# untitled.net
KiCad netlist of a schematic drawn in EAGLE
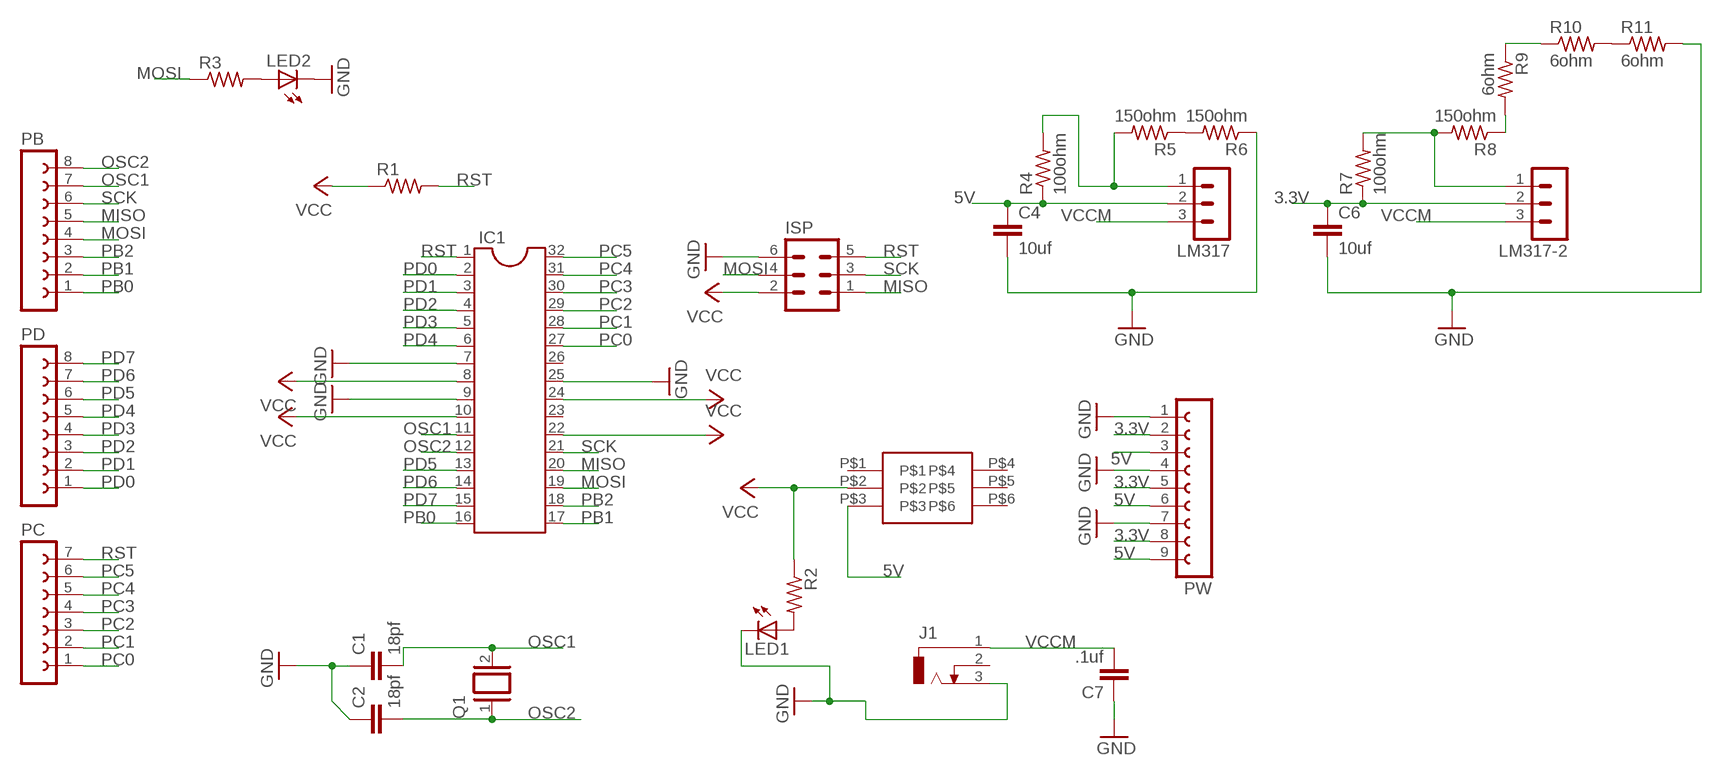
[diagram p0: schematic, sheet 1]

(export (version "E")
  (design (tool "Eeschema 10.0.6"))
  (components
    (comp (ref "C1")
      (value "18pf")
      (footprint "eagle-import:C2.5-2")
      (libsource (lib "eagle-import") (part "C2.5/2"))
    )
    (comp (ref "C2")
      (value "18pf")
      (footprint "eagle-import:C2.5-2")
      (libsource (lib "eagle-import") (part "C2.5/2"))
    )
    (comp (ref "C4")
      (value "10uf")
      (footprint "eagle-import:C15B5")
      (libsource (lib "eagle-import") (part "C15/5"))
    )
    (comp (ref "C6")
      (value "10uf")
      (footprint "eagle-import:C15B5")
      (libsource (lib "eagle-import") (part "C15/5"))
    )
    (comp (ref "C7")
      (value ".1uf")
      (footprint "eagle-import:C5B2.5")
      (libsource (lib "eagle-import") (part "C5/2.5"))
    )
    (comp (ref "IC1")
      (value "DIL32")
      (footprint "eagle-import:DIL32")
      (libsource (lib "eagle-import") (part "DIL32"))
    )
    (comp (ref "ISP")
      (value "MA03-2")
      (footprint "eagle-import:MA03-2")
      (libsource (lib "eagle-import") (part "MA03-2"))
    )
    (comp (ref "J1")
      (value "DCJ0303")
      (footprint "eagle-import:DCJ0303")
      (libsource (lib "eagle-import") (part "DCJ0303"))
    )
    (comp (ref "LED1")
      (value "LED3MM")
      (footprint "eagle-import:LED3MM")
      (libsource (lib "eagle-import") (part "LED3MM"))
    )
    (comp (ref "LED2")
      (value "LED5MM")
      (footprint "eagle-import:LED5MM")
      (libsource (lib "eagle-import") (part "LED5MM"))
    )
    (comp (ref "LM317")
      (value "MA03-1")
      (footprint "eagle-import:MA03-1")
      (libsource (lib "eagle-import") (part "MA03-1"))
    )
    (comp (ref "LM317-2")
      (value "MA03-1")
      (footprint "eagle-import:MA03-1")
      (libsource (lib "eagle-import") (part "MA03-1"))
    )
    (comp (ref "PB")
      (value "FE08-1")
      (footprint "eagle-import:FE08")
      (libsource (lib "eagle-import") (part "FE08-1"))
    )
    (comp (ref "PC")
      (value "FE07-1")
      (footprint "eagle-import:FE07")
      (libsource (lib "eagle-import") (part "FE07-1"))
    )
    (comp (ref "PD")
      (value "FE08-1")
      (footprint "eagle-import:FE08")
      (libsource (lib "eagle-import") (part "FE08-1"))
    )
    (comp (ref "PW")
      (value "FE09-1")
      (footprint "eagle-import:FE09")
      (libsource (lib "eagle-import") (part "FE09-1"))
    )
    (comp (ref "Q1")
      (value "XTAL/S")
      (footprint "eagle-import:QS")
      (libsource (lib "eagle-import") (part "XTAL/S"))
    )
    (comp (ref "R1")
      (value "R-US_0207/10")
      (footprint "eagle-import:0207_10")
      (libsource (lib "eagle-import") (part "R-US_0207/10"))
    )
    (comp (ref "R2")
      (value "R-US_0207/10")
      (footprint "eagle-import:0207_10")
      (libsource (lib "eagle-import") (part "R-US_0207/10"))
    )
    (comp (ref "R3")
      (value "R-US_0207/10")
      (footprint "eagle-import:0207_10")
      (libsource (lib "eagle-import") (part "R-US_0207/10"))
    )
    (comp (ref "R4")
      (value "100ohm")
      (footprint "eagle-import:0207_10")
      (fields (field (name "MF") "Multicomp Passives") (field (name "MPN") "MC00625W04021220R"))
      (libsource (lib "eagle-import") (part "R-US_0207/10"))
    )
    (comp (ref "R5")
      (value "150ohm")
      (footprint "eagle-import:0207_10")
      (libsource (lib "eagle-import") (part "R-US_0207/10"))
    )
    (comp (ref "R6")
      (value "150ohm")
      (footprint "eagle-import:0207_10")
      (libsource (lib "eagle-import") (part "R-US_0207/10"))
    )
    (comp (ref "R7")
      (value "100ohm")
      (footprint "eagle-import:0207_10")
      (fields (field (name "MF") "Multicomp Passives") (field (name "MPN") "MC00625W04021220R"))
      (libsource (lib "eagle-import") (part "R-US_0207/10"))
    )
    (comp (ref "R8")
      (value "150ohm")
      (footprint "eagle-import:0207_10")
      (libsource (lib "eagle-import") (part "R-US_0207/10"))
    )
    (comp (ref "R9")
      (value "6ohm")
      (footprint "eagle-import:0207_10")
      (libsource (lib "eagle-import") (part "R-US_0207/10"))
    )
    (comp (ref "R10")
      (value "6ohm")
      (footprint "eagle-import:0207_10")
      (libsource (lib "eagle-import") (part "R-US_0207/10"))
    )
    (comp (ref "R11")
      (value "6ohm")
      (footprint "eagle-import:0207_10")
      (libsource (lib "eagle-import") (part "R-US_0207/10"))
    )
    (comp (ref "U$1")
      (value "6PINPUSHSC2BIGJOE-CUSTOM")
      (footprint "eagle-import:6PINPUSH")
      (libsource (lib "eagle-import") (part "6PINPUSHSC2BIGJOE-CUSTOM"))
    )
  )
  (nets
    (net (code "1") (name "/3.3V") (class "Default")
      (node (ref "C6") (pin "1") (pinfunction "1_1") (pintype "passive"))
      (node (ref "LM317-2") (pin "2") (pinfunction "2_2") (pintype "passive"))
      (node (ref "PW") (pin "2") (pinfunction "2_2") (pintype "passive"))
      (node (ref "PW") (pin "5") (pinfunction "5_5") (pintype "passive"))
      (node (ref "PW") (pin "8") (pinfunction "8_8") (pintype "passive"))
      (node (ref "R7") (pin "1") (pinfunction "1_1") (pintype "passive"))
    )
    (net (code "2") (name "/5V") (class "Default")
      (node (ref "C4") (pin "1") (pinfunction "1_1") (pintype "passive"))
      (node (ref "LM317") (pin "2") (pinfunction "2_2") (pintype "passive"))
      (node (ref "PW") (pin "3") (pinfunction "3_3") (pintype "passive"))
      (node (ref "PW") (pin "6") (pinfunction "6_6") (pintype "passive"))
      (node (ref "PW") (pin "9") (pinfunction "9_9") (pintype "passive"))
      (node (ref "R4") (pin "1") (pinfunction "1_1") (pintype "passive"))
      (node (ref "U$1") (pin "P$3") (pinfunction "P$3_P$3") (pintype "bidirectional"))
    )
    (net (code "3") (name "/MISO") (class "Default")
      (node (ref "IC1") (pin "20") (pinfunction "20_20") (pintype "passive"))
      (node (ref "ISP") (pin "1") (pinfunction "1_1") (pintype "passive"))
      (node (ref "PB") (pin "5") (pinfunction "5_5") (pintype "passive"))
    )
    (net (code "4") (name "/MOSI") (class "Default")
      (node (ref "IC1") (pin "19") (pinfunction "19_19") (pintype "passive"))
      (node (ref "ISP") (pin "4") (pinfunction "4_4") (pintype "passive"))
      (node (ref "PB") (pin "4") (pinfunction "4_4") (pintype "passive"))
      (node (ref "R3") (pin "1") (pinfunction "1_1") (pintype "passive"))
    )
    (net (code "5") (name "/OSC1") (class "Default")
      (node (ref "C1") (pin "2") (pinfunction "2_2") (pintype "passive"))
      (node (ref "IC1") (pin "11") (pinfunction "11_11") (pintype "passive"))
      (node (ref "PB") (pin "7") (pinfunction "7_7") (pintype "passive"))
      (node (ref "Q1") (pin "2") (pinfunction "2_2") (pintype "passive"))
    )
    (net (code "6") (name "/OSC2") (class "Default")
      (node (ref "C2") (pin "2") (pinfunction "2_2") (pintype "passive"))
      (node (ref "IC1") (pin "12") (pinfunction "12_12") (pintype "passive"))
      (node (ref "PB") (pin "8") (pinfunction "8_8") (pintype "passive"))
      (node (ref "Q1") (pin "1") (pinfunction "1_1") (pintype "passive"))
    )
    (net (code "7") (name "/PB0") (class "Default")
      (node (ref "IC1") (pin "16") (pinfunction "16_16") (pintype "passive"))
      (node (ref "PB") (pin "1") (pinfunction "1_1") (pintype "passive"))
    )
    (net (code "8") (name "/PB1") (class "Default")
      (node (ref "IC1") (pin "17") (pinfunction "17_17") (pintype "passive"))
      (node (ref "PB") (pin "2") (pinfunction "2_2") (pintype "passive"))
    )
    (net (code "9") (name "/PB2") (class "Default")
      (node (ref "IC1") (pin "18") (pinfunction "18_18") (pintype "passive"))
      (node (ref "PB") (pin "3") (pinfunction "3_3") (pintype "passive"))
    )
    (net (code "10") (name "/PC0") (class "Default")
      (node (ref "IC1") (pin "27") (pinfunction "27_27") (pintype "passive"))
      (node (ref "PC") (pin "1") (pinfunction "1_1") (pintype "passive"))
    )
    (net (code "11") (name "/PC1") (class "Default")
      (node (ref "IC1") (pin "28") (pinfunction "28_28") (pintype "passive"))
      (node (ref "PC") (pin "2") (pinfunction "2_2") (pintype "passive"))
    )
    (net (code "12") (name "/PC2") (class "Default")
      (node (ref "IC1") (pin "29") (pinfunction "29_29") (pintype "passive"))
      (node (ref "PC") (pin "3") (pinfunction "3_3") (pintype "passive"))
    )
    (net (code "13") (name "/PC3") (class "Default")
      (node (ref "IC1") (pin "30") (pinfunction "30_30") (pintype "passive"))
      (node (ref "PC") (pin "4") (pinfunction "4_4") (pintype "passive"))
    )
    (net (code "14") (name "/PC4") (class "Default")
      (node (ref "IC1") (pin "31") (pinfunction "31_31") (pintype "passive"))
      (node (ref "PC") (pin "5") (pinfunction "5_5") (pintype "passive"))
    )
    (net (code "15") (name "/PC5") (class "Default")
      (node (ref "IC1") (pin "32") (pinfunction "32_32") (pintype "passive"))
      (node (ref "PC") (pin "6") (pinfunction "6_6") (pintype "passive"))
    )
    (net (code "16") (name "/PD0") (class "Default")
      (node (ref "IC1") (pin "2") (pinfunction "2_2") (pintype "passive"))
      (node (ref "PD") (pin "1") (pinfunction "1_1") (pintype "passive"))
    )
    (net (code "17") (name "/PD1") (class "Default")
      (node (ref "IC1") (pin "3") (pinfunction "3_3") (pintype "passive"))
      (node (ref "PD") (pin "2") (pinfunction "2_2") (pintype "passive"))
    )
    (net (code "18") (name "/PD2") (class "Default")
      (node (ref "IC1") (pin "4") (pinfunction "4_4") (pintype "passive"))
      (node (ref "PD") (pin "3") (pinfunction "3_3") (pintype "passive"))
    )
    (net (code "19") (name "/PD3") (class "Default")
      (node (ref "IC1") (pin "5") (pinfunction "5_5") (pintype "passive"))
      (node (ref "PD") (pin "4") (pinfunction "4_4") (pintype "passive"))
    )
    (net (code "20") (name "/PD4") (class "Default")
      (node (ref "IC1") (pin "6") (pinfunction "6_6") (pintype "passive"))
      (node (ref "PD") (pin "5") (pinfunction "5_5") (pintype "passive"))
    )
    (net (code "21") (name "/PD5") (class "Default")
      (node (ref "IC1") (pin "13") (pinfunction "13_13") (pintype "passive"))
      (node (ref "PD") (pin "6") (pinfunction "6_6") (pintype "passive"))
    )
    (net (code "22") (name "/PD6") (class "Default")
      (node (ref "IC1") (pin "14") (pinfunction "14_14") (pintype "passive"))
      (node (ref "PD") (pin "7") (pinfunction "7_7") (pintype "passive"))
    )
    (net (code "23") (name "/PD7") (class "Default")
      (node (ref "IC1") (pin "15") (pinfunction "15_15") (pintype "passive"))
      (node (ref "PD") (pin "8") (pinfunction "8_8") (pintype "passive"))
    )
    (net (code "24") (name "/RST") (class "Default")
      (node (ref "IC1") (pin "1") (pinfunction "1_1") (pintype "passive"))
      (node (ref "ISP") (pin "5") (pinfunction "5_5") (pintype "passive"))
      (node (ref "PC") (pin "7") (pinfunction "7_7") (pintype "passive"))
      (node (ref "R1") (pin "2") (pinfunction "2_2") (pintype "passive"))
    )
    (net (code "25") (name "/SCK") (class "Default")
      (node (ref "IC1") (pin "21") (pinfunction "21_21") (pintype "passive"))
      (node (ref "ISP") (pin "3") (pinfunction "3_3") (pintype "passive"))
      (node (ref "PB") (pin "6") (pinfunction "6_6") (pintype "passive"))
    )
    (net (code "26") (name "/VCCM") (class "Default")
      (node (ref "C7") (pin "2") (pinfunction "2_2") (pintype "passive"))
      (node (ref "J1") (pin "1") (pinfunction "1_1") (pintype "passive"))
      (node (ref "LM317") (pin "3") (pinfunction "3_3") (pintype "passive"))
      (node (ref "LM317-2") (pin "3") (pinfunction "3_3") (pintype "passive"))
    )
    (net (code "27") (name "GND") (class "Default")
      (node (ref "C1") (pin "1") (pinfunction "1_1") (pintype "passive"))
      (node (ref "C2") (pin "1") (pinfunction "1_1") (pintype "passive"))
      (node (ref "C4") (pin "2") (pinfunction "2_2") (pintype "passive"))
      (node (ref "C6") (pin "2") (pinfunction "2_2") (pintype "passive"))
      (node (ref "C7") (pin "1") (pinfunction "1_1") (pintype "passive"))
      (node (ref "IC1") (pin "25") (pinfunction "25_25") (pintype "passive"))
      (node (ref "IC1") (pin "7") (pinfunction "7_7") (pintype "passive"))
      (node (ref "IC1") (pin "9") (pinfunction "9_9") (pintype "passive"))
      (node (ref "ISP") (pin "6") (pinfunction "6_6") (pintype "passive"))
      (node (ref "J1") (pin "3") (pinfunction "3_3") (pintype "passive"))
      (node (ref "LED1") (pin "K") (pinfunction "C_K") (pintype "passive"))
      (node (ref "LED2") (pin "K") (pinfunction "C_K") (pintype "passive"))
      (node (ref "PW") (pin "1") (pinfunction "1_1") (pintype "passive"))
      (node (ref "PW") (pin "4") (pinfunction "4_4") (pintype "passive"))
      (node (ref "PW") (pin "7") (pinfunction "7_7") (pintype "passive"))
      (node (ref "R11") (pin "2") (pinfunction "2_2") (pintype "passive"))
      (node (ref "R6") (pin "1") (pinfunction "1_1") (pintype "passive"))
    )
    (net (code "28") (name "Net-(LED1-PadA)") (class "Default")
      (node (ref "LED1") (pin "A") (pinfunction "A_A") (pintype "passive"))
      (node (ref "R2") (pin "2") (pinfunction "2_2") (pintype "passive"))
    )
    (net (code "29") (name "Net-(LED2-PadA)") (class "Default")
      (node (ref "LED2") (pin "A") (pinfunction "A_A") (pintype "passive"))
      (node (ref "R3") (pin "2") (pinfunction "2_2") (pintype "passive"))
    )
    (net (code "30") (name "Net-(LM317-2-Pad1)") (class "Default")
      (node (ref "LM317-2") (pin "1") (pinfunction "1_1") (pintype "passive"))
      (node (ref "R7") (pin "2") (pinfunction "2_2") (pintype "passive"))
      (node (ref "R8") (pin "2") (pinfunction "2_2") (pintype "passive"))
    )
    (net (code "31") (name "Net-(LM317-Pad1)") (class "Default")
      (node (ref "LM317") (pin "1") (pinfunction "1_1") (pintype "passive"))
      (node (ref "R4") (pin "2") (pinfunction "2_2") (pintype "passive"))
      (node (ref "R5") (pin "2") (pinfunction "2_2") (pintype "passive"))
    )
    (net (code "32") (name "Net-(R5-Pad1)") (class "Default")
      (node (ref "R5") (pin "1") (pinfunction "1_1") (pintype "passive"))
      (node (ref "R6") (pin "2") (pinfunction "2_2") (pintype "passive"))
    )
    (net (code "33") (name "Net-(R8-Pad1)") (class "Default")
      (node (ref "R8") (pin "1") (pinfunction "1_1") (pintype "passive"))
      (node (ref "R9") (pin "2") (pinfunction "2_2") (pintype "passive"))
    )
    (net (code "34") (name "Net-(R10-Pad1)") (class "Default")
      (node (ref "R10") (pin "1") (pinfunction "1_1") (pintype "passive"))
      (node (ref "R9") (pin "1") (pinfunction "1_1") (pintype "passive"))
    )
    (net (code "35") (name "Net-(R10-Pad2)") (class "Default")
      (node (ref "R10") (pin "2") (pinfunction "2_2") (pintype "passive"))
      (node (ref "R11") (pin "1") (pinfunction "1_1") (pintype "passive"))
    )
    (net (code "36") (name "VCC") (class "Default")
      (node (ref "IC1") (pin "10") (pinfunction "10_10") (pintype "passive"))
      (node (ref "IC1") (pin "22") (pinfunction "22_22") (pintype "passive"))
      (node (ref "IC1") (pin "24") (pinfunction "24_24") (pintype "passive"))
      (node (ref "IC1") (pin "8") (pinfunction "8_8") (pintype "passive"))
      (node (ref "ISP") (pin "2") (pinfunction "2_2") (pintype "passive"))
      (node (ref "R1") (pin "1") (pinfunction "1_1") (pintype "passive"))
      (node (ref "R2") (pin "1") (pinfunction "1_1") (pintype "passive"))
      (node (ref "U$1") (pin "P$2") (pinfunction "P$2_P$2") (pintype "bidirectional"))
    )
    (net (code "37") (name "unconnected-(IC1-Pad23)") (class "Default")
      (node (ref "IC1") (pin "23") (pinfunction "23_23") (pintype "passive"))
    )
    (net (code "38") (name "unconnected-(IC1-Pad26)") (class "Default")
      (node (ref "IC1") (pin "26") (pinfunction "26_26") (pintype "passive"))
    )
    (net (code "39") (name "unconnected-(J1-Pad2)") (class "Default")
      (node (ref "J1") (pin "2") (pinfunction "2_2") (pintype "passive"))
    )
    (net (code "40") (name "unconnected-(U$1-PadP$1)") (class "Default")
      (node (ref "U$1") (pin "P$1") (pinfunction "P$1_P$1") (pintype "bidirectional"))
    )
    (net (code "41") (name "unconnected-(U$1-PadP$4)") (class "Default")
      (node (ref "U$1") (pin "P$4") (pinfunction "P$4_P$4") (pintype "bidirectional"))
    )
    (net (code "42") (name "unconnected-(U$1-PadP$5)") (class "Default")
      (node (ref "U$1") (pin "P$5") (pinfunction "P$5_P$5") (pintype "bidirectional"))
    )
    (net (code "43") (name "unconnected-(U$1-PadP$6)") (class "Default")
      (node (ref "U$1") (pin "P$6") (pinfunction "P$6_P$6") (pintype "bidirectional"))
    )
  )
)
